# audio_amp_hf.net
KiCad netlist of a schematic drawn in Altium Designer
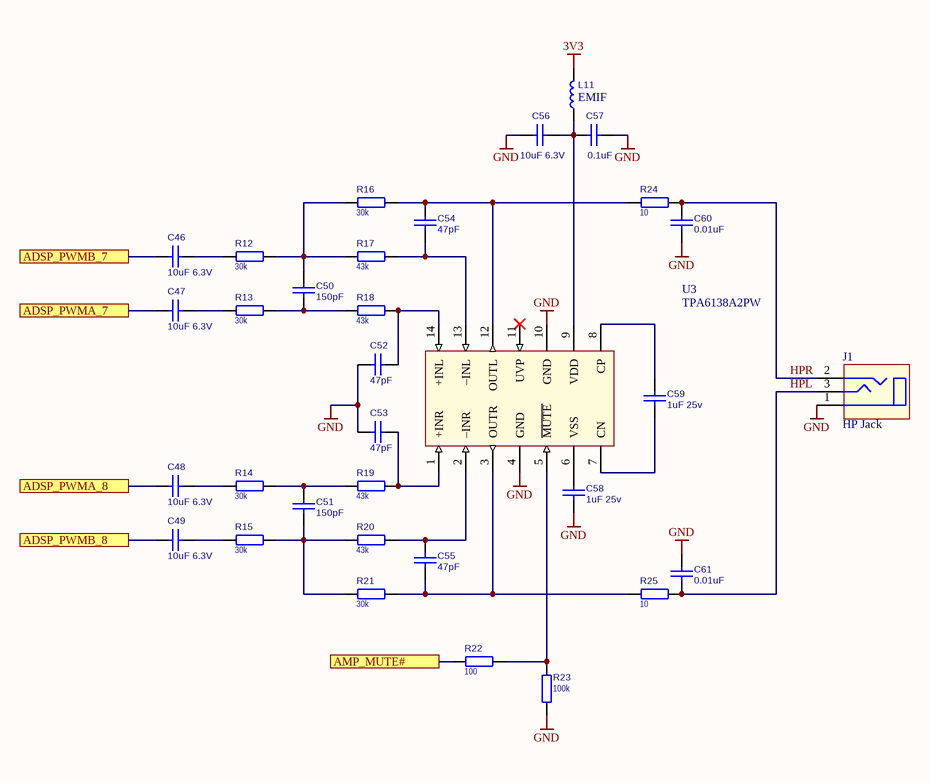
[diagram p0: audio_amp_hf.SchDoc]

(export (version "E")
  (design (tool "Eeschema 10.0.6"))
  (components
    (comp (ref "C46")
      (value "10uF 6.3V")
      (footprint "Capacitors:C0603")
      (description "CAP_NPOL")
      (fields (field (name "Comment") "CC0603MRX5R5BB106"))
      (libsource (lib "capacitors") (part "CAP_NPOL"))
    )
    (comp (ref "C47")
      (value "10uF 6.3V")
      (footprint "Capacitors:C0603")
      (description "CAP_NPOL")
      (fields (field (name "Comment") "CC0603MRX5R5BB106"))
      (libsource (lib "capacitors") (part "CAP_NPOL"))
    )
    (comp (ref "C48")
      (value "10uF 6.3V")
      (footprint "Capacitors:C0603")
      (description "CAP_NPOL")
      (fields (field (name "Comment") "CC0603MRX5R5BB106"))
      (libsource (lib "capacitors") (part "CAP_NPOL"))
    )
    (comp (ref "C49")
      (value "10uF 6.3V")
      (footprint "Capacitors:C0603")
      (description "CAP_NPOL")
      (fields (field (name "Comment") "CC0603MRX5R5BB106"))
      (libsource (lib "capacitors") (part "CAP_NPOL"))
    )
    (comp (ref "C50")
      (value "150pF")
      (footprint "Capacitors:C0603")
      (description "CAP_NPOL")
      (fields (field (name "Comment") "CC0603JRNPO9BN151"))
      (libsource (lib "capacitors") (part "CAP_NPOL"))
    )
    (comp (ref "C51")
      (value "150pF")
      (footprint "Capacitors:C0603")
      (description "CAP_NPOL")
      (fields (field (name "Comment") "CC0603JRNPO9BN151"))
      (libsource (lib "capacitors") (part "CAP_NPOL"))
    )
    (comp (ref "C52")
      (value "47pF")
      (footprint "Capacitors:C0603")
      (description "CAP_NPOL")
      (fields (field (name "Comment") "CC0603JRNPO9BN470"))
      (libsource (lib "capacitors") (part "CAP_NPOL"))
    )
    (comp (ref "C53")
      (value "47pF")
      (footprint "Capacitors:C0603")
      (description "CAP_NPOL")
      (fields (field (name "Comment") "CC0603JRNPO9BN470"))
      (libsource (lib "capacitors") (part "CAP_NPOL"))
    )
    (comp (ref "C54")
      (value "47pF")
      (footprint "Capacitors:C0603")
      (description "CAP_NPOL")
      (fields (field (name "Comment") "CC0603JRNPO9BN470"))
      (libsource (lib "capacitors") (part "CAP_NPOL"))
    )
    (comp (ref "C55")
      (value "47pF")
      (footprint "Capacitors:C0603")
      (description "CAP_NPOL")
      (fields (field (name "Comment") "CC0603JRNPO9BN470"))
      (libsource (lib "capacitors") (part "CAP_NPOL"))
    )
    (comp (ref "C56")
      (value "10uF 6.3V")
      (footprint "Capacitors:C0603")
      (description "CAP_NPOL")
      (fields (field (name "Comment") "CC0603MRX5R5BB106"))
      (libsource (lib "capacitors") (part "CAP_NPOL"))
    )
    (comp (ref "C57")
      (value "0.1uF")
      (footprint "Capacitors:C0603")
      (description "CAP_NPOL")
      (fields (field (name "Comment") "C1608X7R1H104K080AA"))
      (libsource (lib "capacitors") (part "CAP_NPOL"))
    )
    (comp (ref "C58")
      (value "1uF 25v")
      (footprint "Capacitors:C0603")
      (description "CAP_NPOL")
      (fields (field (name "Comment") "GRM188R61E105KA12D"))
      (libsource (lib "capacitors") (part "CAP_NPOL"))
    )
    (comp (ref "C59")
      (value "1uF 25v")
      (footprint "Capacitors:C0603")
      (description "CAP_NPOL")
      (fields (field (name "Comment") "GRM188R61E105KA12D"))
      (libsource (lib "capacitors") (part "CAP_NPOL"))
    )
    (comp (ref "C60")
      (value "0.01uF")
      (footprint "Capacitors:C0603")
      (description "CAP_NPOL")
      (fields (field (name "Comment") "CL10B103KB8NNNC"))
      (libsource (lib "capacitors") (part "CAP_NPOL"))
    )
    (comp (ref "C61")
      (value "0.01uF")
      (footprint "Capacitors:C0603")
      (description "CAP_NPOL")
      (fields (field (name "Comment") "CL10B103KB8NNNC"))
      (libsource (lib "capacitors") (part "CAP_NPOL"))
    )
    (comp (ref "J1")
      (value "HP Jack")
      (footprint "AUB-13")
      (description "Phonejack Stereo")
      (fields (field (name "Comment") "AUB-13"))
      (libsource (lib "PhoneJack") (part "PhoneJack"))
    )
    (comp (ref "L11")
      (value "EMIF")
      (footprint "IND0603")
      (description "IND_WO_IRON")
      (fields (field (name "Comment") "BLM18AG102SN1D"))
      (libsource (lib "inductors") (part "IND_WO_IRON"))
    )
    (comp (ref "R12")
      (value "30k")
      (footprint "R0603")
      (description "RES")
      (libsource (lib "resistors") (part "RESISTOR"))
    )
    (comp (ref "R13")
      (value "30k")
      (footprint "R0603")
      (description "RES")
      (libsource (lib "resistors") (part "RESISTOR"))
    )
    (comp (ref "R14")
      (value "30k")
      (footprint "R0603")
      (description "RES")
      (libsource (lib "resistors") (part "RESISTOR"))
    )
    (comp (ref "R15")
      (value "30k")
      (footprint "R0603")
      (description "RES")
      (libsource (lib "resistors") (part "RESISTOR"))
    )
    (comp (ref "R16")
      (value "30k")
      (footprint "R0603")
      (description "RES")
      (libsource (lib "resistors") (part "RESISTOR"))
    )
    (comp (ref "R17")
      (value "43k")
      (footprint "R0603")
      (description "RES")
      (libsource (lib "resistors") (part "RESISTOR"))
    )
    (comp (ref "R18")
      (value "43k")
      (footprint "R0603")
      (description "RES")
      (libsource (lib "resistors") (part "RESISTOR"))
    )
    (comp (ref "R19")
      (value "43k")
      (footprint "R0603")
      (description "RES")
      (libsource (lib "resistors") (part "RESISTOR"))
    )
    (comp (ref "R20")
      (value "43k")
      (footprint "R0603")
      (description "RES")
      (libsource (lib "resistors") (part "RESISTOR"))
    )
    (comp (ref "R21")
      (value "30k")
      (footprint "R0603")
      (description "RES")
      (libsource (lib "resistors") (part "RESISTOR"))
    )
    (comp (ref "R22")
      (value "100")
      (footprint "Resistors:R0603")
      (description "RES")
      (libsource (lib "resistors") (part "RESISTOR"))
    )
    (comp (ref "R23")
      (value "100k")
      (footprint "R0603")
      (description "RES")
      (libsource (lib "resistors") (part "RESISTOR"))
    )
    (comp (ref "R24")
      (value "10")
      (footprint "Resistors:R0805")
      (description "RES")
      (libsource (lib "resistors") (part "RESISTOR"))
    )
    (comp (ref "R25")
      (value "10")
      (footprint "Resistors:R0805")
      (description "RES")
      (libsource (lib "resistors") (part "RESISTOR"))
    )
    (comp (ref "U3")
      (value "TPA6138A2PW")
      (footprint "TSSOP-14")
      (description "DirectPath™ Headphone Driver With Adjustable Gain")
      (libsource (lib "TPA6138A2") (part "TPA6138A2"))
    )
  )
  (nets
    (net (code "1") (name "/ADSP_PWMA_7") (class "Default")
      (node (ref "C47") (pin "2") (pinfunction "2_2") (pintype "passive"))
    )
    (net (code "2") (name "/ADSP_PWMA_8") (class "Default")
      (node (ref "C48") (pin "2") (pinfunction "2_2") (pintype "passive"))
    )
    (net (code "3") (name "/ADSP_PWMB_7") (class "Default")
      (node (ref "C46") (pin "2") (pinfunction "2_2") (pintype "passive"))
    )
    (net (code "4") (name "/ADSP_PWMB_8") (class "Default")
      (node (ref "C49") (pin "2") (pinfunction "2_2") (pintype "passive"))
    )
    (net (code "5") (name "/AMP_MUTE#") (class "Default")
      (node (ref "R22") (pin "1") (pinfunction "1_1") (pintype "passive"))
    )
    (net (code "6") (name "/HPL") (class "Default")
      (node (ref "C61") (pin "1") (pinfunction "1_1") (pintype "passive"))
      (node (ref "J1") (pin "3") (pinfunction "L_3") (pintype "passive"))
      (node (ref "R25") (pin "1") (pinfunction "1_1") (pintype "passive"))
    )
    (net (code "7") (name "/HPR") (class "Default")
      (node (ref "C60") (pin "2") (pinfunction "2_2") (pintype "passive"))
      (node (ref "J1") (pin "2") (pinfunction "R_2") (pintype "passive"))
      (node (ref "R24") (pin "1") (pinfunction "1_1") (pintype "passive"))
    )
    (net (code "8") (name "3V3") (class "Default") (node (ref "L11") (pin "2") (pintype "passive")))
    (net (code "9") (name "GND") (class "Default")
      (node (ref "C52") (pin "2") (pinfunction "2_2") (pintype "passive"))
      (node (ref "C53") (pin "2") (pinfunction "2_2") (pintype "passive"))
      (node (ref "C56") (pin "2") (pinfunction "2_2") (pintype "passive"))
      (node (ref "C57") (pin "1") (pinfunction "1_1") (pintype "passive"))
      (node (ref "C58") (pin "1") (pinfunction "1_1") (pintype "passive"))
      (node (ref "C60") (pin "1") (pinfunction "1_1") (pintype "passive"))
      (node (ref "C61") (pin "2") (pinfunction "2_2") (pintype "passive"))
      (node (ref "J1") (pin "1") (pinfunction "C_1") (pintype "passive"))
      (node (ref "R23") (pin "2") (pinfunction "2_2") (pintype "passive"))
      (node (ref "U3") (pin "10") (pinfunction "GND_10") (pintype "power_in"))
      (node (ref "U3") (pin "4") (pinfunction "GND_4") (pintype "power_in"))
    )
    (net (code "10") (name "Net-(C46-Pad1)") (class "Default")
      (node (ref "C46") (pin "1") (pinfunction "1_1") (pintype "passive"))
      (node (ref "R12") (pin "2") (pinfunction "2_2") (pintype "passive"))
    )
    (net (code "11") (name "Net-(C47-Pad1)") (class "Default")
      (node (ref "C47") (pin "1") (pinfunction "1_1") (pintype "passive"))
      (node (ref "R13") (pin "2") (pinfunction "2_2") (pintype "passive"))
    )
    (net (code "12") (name "Net-(C48-Pad1)") (class "Default")
      (node (ref "C48") (pin "1") (pinfunction "1_1") (pintype "passive"))
      (node (ref "R14") (pin "2") (pinfunction "2_2") (pintype "passive"))
    )
    (net (code "13") (name "Net-(C49-Pad1)") (class "Default")
      (node (ref "C49") (pin "1") (pinfunction "1_1") (pintype "passive"))
      (node (ref "R15") (pin "2") (pinfunction "2_2") (pintype "passive"))
    )
    (net (code "14") (name "Net-(C50-Pad1)") (class "Default")
      (node (ref "C50") (pin "1") (pinfunction "1_1") (pintype "passive"))
      (node (ref "R13") (pin "1") (pinfunction "1_1") (pintype "passive"))
      (node (ref "R18") (pin "2") (pinfunction "2_2") (pintype "passive"))
    )
    (net (code "15") (name "Net-(C50-Pad2)") (class "Default")
      (node (ref "C50") (pin "2") (pinfunction "2_2") (pintype "passive"))
      (node (ref "R12") (pin "1") (pinfunction "1_1") (pintype "passive"))
      (node (ref "R16") (pin "2") (pinfunction "2_2") (pintype "passive"))
      (node (ref "R17") (pin "2") (pinfunction "2_2") (pintype "passive"))
    )
    (net (code "16") (name "Net-(C51-Pad1)") (class "Default")
      (node (ref "C51") (pin "1") (pinfunction "1_1") (pintype "passive"))
      (node (ref "R15") (pin "1") (pinfunction "1_1") (pintype "passive"))
      (node (ref "R20") (pin "2") (pinfunction "2_2") (pintype "passive"))
      (node (ref "R21") (pin "2") (pinfunction "2_2") (pintype "passive"))
    )
    (net (code "17") (name "Net-(C51-Pad2)") (class "Default")
      (node (ref "C51") (pin "2") (pinfunction "2_2") (pintype "passive"))
      (node (ref "R14") (pin "1") (pinfunction "1_1") (pintype "passive"))
      (node (ref "R19") (pin "2") (pinfunction "2_2") (pintype "passive"))
    )
    (net (code "18") (name "Net-(U3-+INL)") (class "Default")
      (node (ref "C52") (pin "1") (pinfunction "1_1") (pintype "passive"))
      (node (ref "R18") (pin "1") (pinfunction "1_1") (pintype "passive"))
      (node (ref "U3") (pin "14") (pinfunction "+INL_14") (pintype "input"))
    )
    (net (code "19") (name "Net-(U3-+INR)") (class "Default")
      (node (ref "C53") (pin "1") (pinfunction "1_1") (pintype "passive"))
      (node (ref "R19") (pin "1") (pinfunction "1_1") (pintype "passive"))
      (node (ref "U3") (pin "1") (pinfunction "+INR_1") (pintype "input"))
    )
    (net (code "20") (name "Net-(U3-CN)") (class "Default")
      (node (ref "C59") (pin "1") (pinfunction "1_1") (pintype "passive"))
      (node (ref "U3") (pin "7") (pinfunction "CN_7") (pintype "passive"))
    )
    (net (code "21") (name "Net-(U3-CP)") (class "Default")
      (node (ref "C59") (pin "2") (pinfunction "2_2") (pintype "passive"))
      (node (ref "U3") (pin "8") (pinfunction "CP_8") (pintype "passive"))
    )
    (net (code "22") (name "Net-(U3-OUTL)") (class "Default")
      (node (ref "C54") (pin "2") (pinfunction "2_2") (pintype "passive"))
      (node (ref "R16") (pin "1") (pinfunction "1_1") (pintype "passive"))
      (node (ref "R24") (pin "2") (pinfunction "2_2") (pintype "passive"))
      (node (ref "U3") (pin "12") (pinfunction "OUTL_12") (pintype "output"))
    )
    (net (code "23") (name "Net-(U3-OUTR)") (class "Default")
      (node (ref "C55") (pin "1") (pinfunction "1_1") (pintype "passive"))
      (node (ref "R21") (pin "1") (pinfunction "1_1") (pintype "passive"))
      (node (ref "R25") (pin "2") (pinfunction "2_2") (pintype "passive"))
      (node (ref "U3") (pin "3") (pinfunction "OUTR_3") (pintype "output"))
    )
    (net (code "24") (name "Net-(U3-VDD)") (class "Default")
      (node (ref "C56") (pin "1") (pinfunction "1_1") (pintype "passive"))
      (node (ref "C57") (pin "2") (pinfunction "2_2") (pintype "passive"))
      (node (ref "L11") (pin "1") (pintype "passive"))
      (node (ref "U3") (pin "9") (pinfunction "VDD_9") (pintype "passive"))
    )
    (net (code "25") (name "Net-(U3-VSS)") (class "Default")
      (node (ref "C58") (pin "2") (pinfunction "2_2") (pintype "passive"))
      (node (ref "U3") (pin "6") (pinfunction "VSS_6") (pintype "power_in"))
    )
    (net (code "26") (name "Net-(U3-~{MUTE})") (class "Default")
      (node (ref "R22") (pin "2") (pinfunction "2_2") (pintype "passive"))
      (node (ref "R23") (pin "1") (pinfunction "1_1") (pintype "passive"))
      (node (ref "U3") (pin "5") (pinfunction "~{MUTE}_5") (pintype "input"))
    )
    (net (code "27") (name "Net-(U3-–INL)") (class "Default")
      (node (ref "C54") (pin "1") (pinfunction "1_1") (pintype "passive"))
      (node (ref "R17") (pin "1") (pinfunction "1_1") (pintype "passive"))
      (node (ref "U3") (pin "13") (pinfunction "–INL_13") (pintype "input"))
    )
    (net (code "28") (name "Net-(U3-–INR)") (class "Default")
      (node (ref "C55") (pin "2") (pinfunction "2_2") (pintype "passive"))
      (node (ref "R20") (pin "1") (pinfunction "1_1") (pintype "passive"))
      (node (ref "U3") (pin "2") (pinfunction "–INR_2") (pintype "input"))
    )
    (net (code "29") (name "unconnected-(U3-UVP-Pad11)") (class "Default")
      (node (ref "U3") (pin "11") (pinfunction "UVP_11") (pintype "input+no_connect"))
    )
  )
)
